# USB-Knob.net
KiCad netlist of a schematic drawn in EAGLE
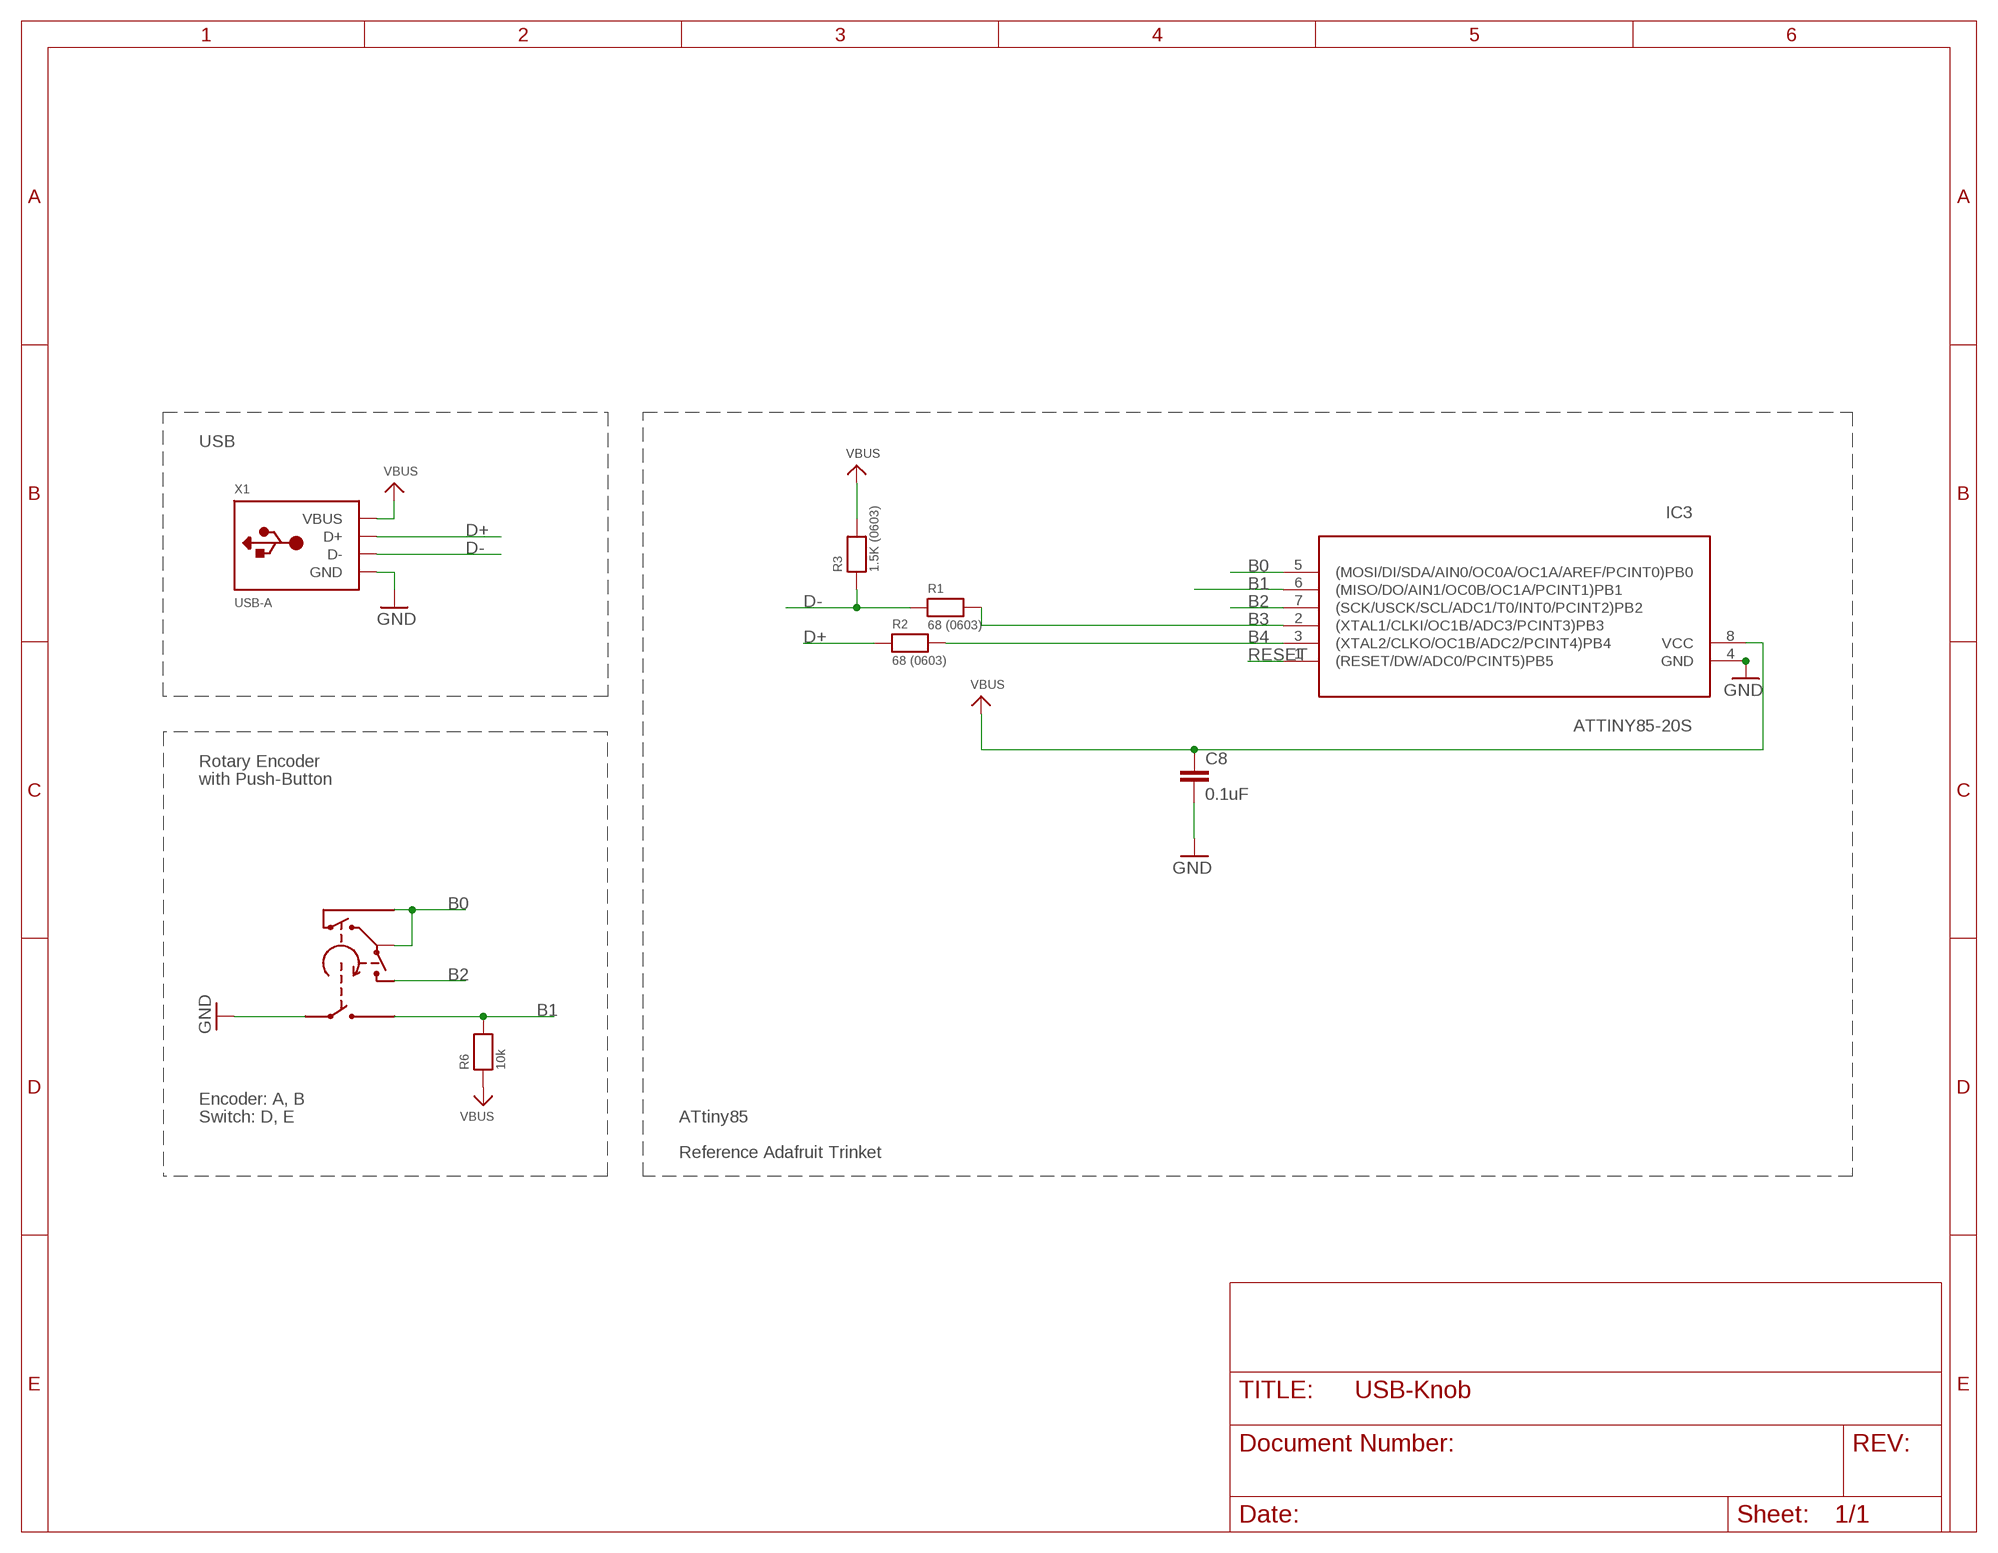
[diagram p0: schematic, sheet 1]

(export (version "E")
  (design (tool "Eeschema 10.0.6"))
  (components
    (comp (ref "C8")
      (value "0.1uF")
      (footprint "eagle-import:0603-CAP")
      (libsource (lib "eagle-import") (part "CAP0603-CAP"))
    )
    (comp (ref "IC3")
      (value "ATTINY85-20S")
      (footprint "eagle-import:SOIC8")
      (libsource (lib "eagle-import") (part "ATTINY85SV-10"))
    )
    (comp (ref "R1")
      (value "68 (0603)")
      (footprint "eagle-import:0603-NO")
      (libsource (lib "eagle-import") (part "RESISTOR_0603_NOOUT"))
    )
    (comp (ref "R2")
      (value "68 (0603)")
      (footprint "eagle-import:0603-NO")
      (libsource (lib "eagle-import") (part "RESISTOR_0603_NOOUT"))
    )
    (comp (ref "R3")
      (value "1.5K (0603)")
      (footprint "eagle-import:0603-NO")
      (libsource (lib "eagle-import") (part "RESISTOR_0603_NOOUT"))
    )
    (comp (ref "R6")
      (value "10k")
      (footprint "eagle-import:0603-NO")
      (libsource (lib "eagle-import") (part "RESISTOR_0603_NOOUT"))
    )
    (comp (ref "U$1")
      (value "EVE-S")
      (footprint "eagle-import:EVE-S")
      (libsource (lib "eagle-import") (part "EVE-S"))
    )
    (comp (ref "X1")
      (value "USB-A")
      (footprint "eagle-import:MOLEX_480371000")
      (libsource (lib "eagle-import") (part "USB-A"))
    )
  )
  (nets
    (net (code "1") (name "/B0") (class "Default")
      (node (ref "IC3") (pin "5") (pinfunction "(MOSI/DI/SDA/AIN0/OC0A/OC1A/AREF/PCINT0)PB0_5") (pintype "bidirectional"))
      (node (ref "U$1") (pin "1") (pinfunction "A_1") (pintype "passive"))
      (node (ref "U$1") (pin "GND0") (pinfunction "COM_GND0") (pintype "passive"))
      (node (ref "U$1") (pin "GND1") (pinfunction "COM_GND1") (pintype "passive"))
      (node (ref "U$1") (pin "GND2") (pinfunction "COM_GND2") (pintype "passive"))
    )
    (net (code "2") (name "/B1") (class "Default")
      (node (ref "IC3") (pin "6") (pinfunction "(MISO/DO/AIN1/OC0B/OC1A/PCINT1)PB1_6") (pintype "bidirectional"))
      (node (ref "R6") (pin "2") (pinfunction "2_2") (pintype "passive"))
      (node (ref "U$1") (pin "B2") (pinfunction "S2_B2") (pintype "passive"))
    )
    (net (code "3") (name "/B2") (class "Default")
      (node (ref "IC3") (pin "7") (pinfunction "(SCK/USCK/SCL/ADC1/T0/INT0/PCINT2)PB2_7") (pintype "bidirectional"))
      (node (ref "U$1") (pin "2") (pinfunction "B_2") (pintype "passive"))
    )
    (net (code "4") (name "/B3") (class "Default")
      (node (ref "IC3") (pin "2") (pinfunction "(XTAL1/CLKI/OC1B/ADC3/PCINT3)PB3_2") (pintype "bidirectional"))
      (node (ref "R1") (pin "2") (pinfunction "2_2") (pintype "passive"))
    )
    (net (code "5") (name "/B4") (class "Default")
      (node (ref "IC3") (pin "3") (pinfunction "(XTAL2/CLKO/OC1B/ADC2/PCINT4)PB4_3") (pintype "bidirectional"))
      (node (ref "R2") (pin "2") (pinfunction "2_2") (pintype "passive"))
    )
    (net (code "6") (name "/D+") (class "Default")
      (node (ref "R2") (pin "1") (pinfunction "1_1") (pintype "passive"))
      (node (ref "X1") (pin "3") (pinfunction "D+_3") (pintype "bidirectional"))
    )
    (net (code "7") (name "/D-") (class "Default")
      (node (ref "R1") (pin "1") (pinfunction "1_1") (pintype "passive"))
      (node (ref "R3") (pin "1") (pinfunction "1_1") (pintype "passive"))
      (node (ref "X1") (pin "2") (pinfunction "D-_2") (pintype "bidirectional"))
    )
    (net (code "8") (name "/RESET") (class "Default")
      (node (ref "IC3") (pin "1") (pinfunction "(RESET/DW/ADC0/PCINT5)PB5_1") (pintype "bidirectional"))
    )
    (net (code "9") (name "GND") (class "Default")
      (node (ref "C8") (pin "2") (pinfunction "2_2") (pintype "passive"))
      (node (ref "IC3") (pin "4") (pinfunction "GND_4") (pintype "bidirectional"))
      (node (ref "U$1") (pin "B1") (pinfunction "S1_B1") (pintype "passive"))
      (node (ref "X1") (pin "4") (pinfunction "GND_4") (pintype "power_in"))
    )
    (net (code "10") (name "VBUS") (class "Default")
      (node (ref "C8") (pin "1") (pinfunction "1_1") (pintype "passive"))
      (node (ref "IC3") (pin "8") (pinfunction "VCC_8") (pintype "bidirectional"))
      (node (ref "R3") (pin "2") (pinfunction "2_2") (pintype "passive"))
      (node (ref "R6") (pin "1") (pinfunction "1_1") (pintype "passive"))
      (node (ref "X1") (pin "1") (pinfunction "VBUS_1") (pintype "power_in"))
    )
  )
)
